# ControlBoardEsp.net
KiCad netlist of a schematic drawn in EAGLE
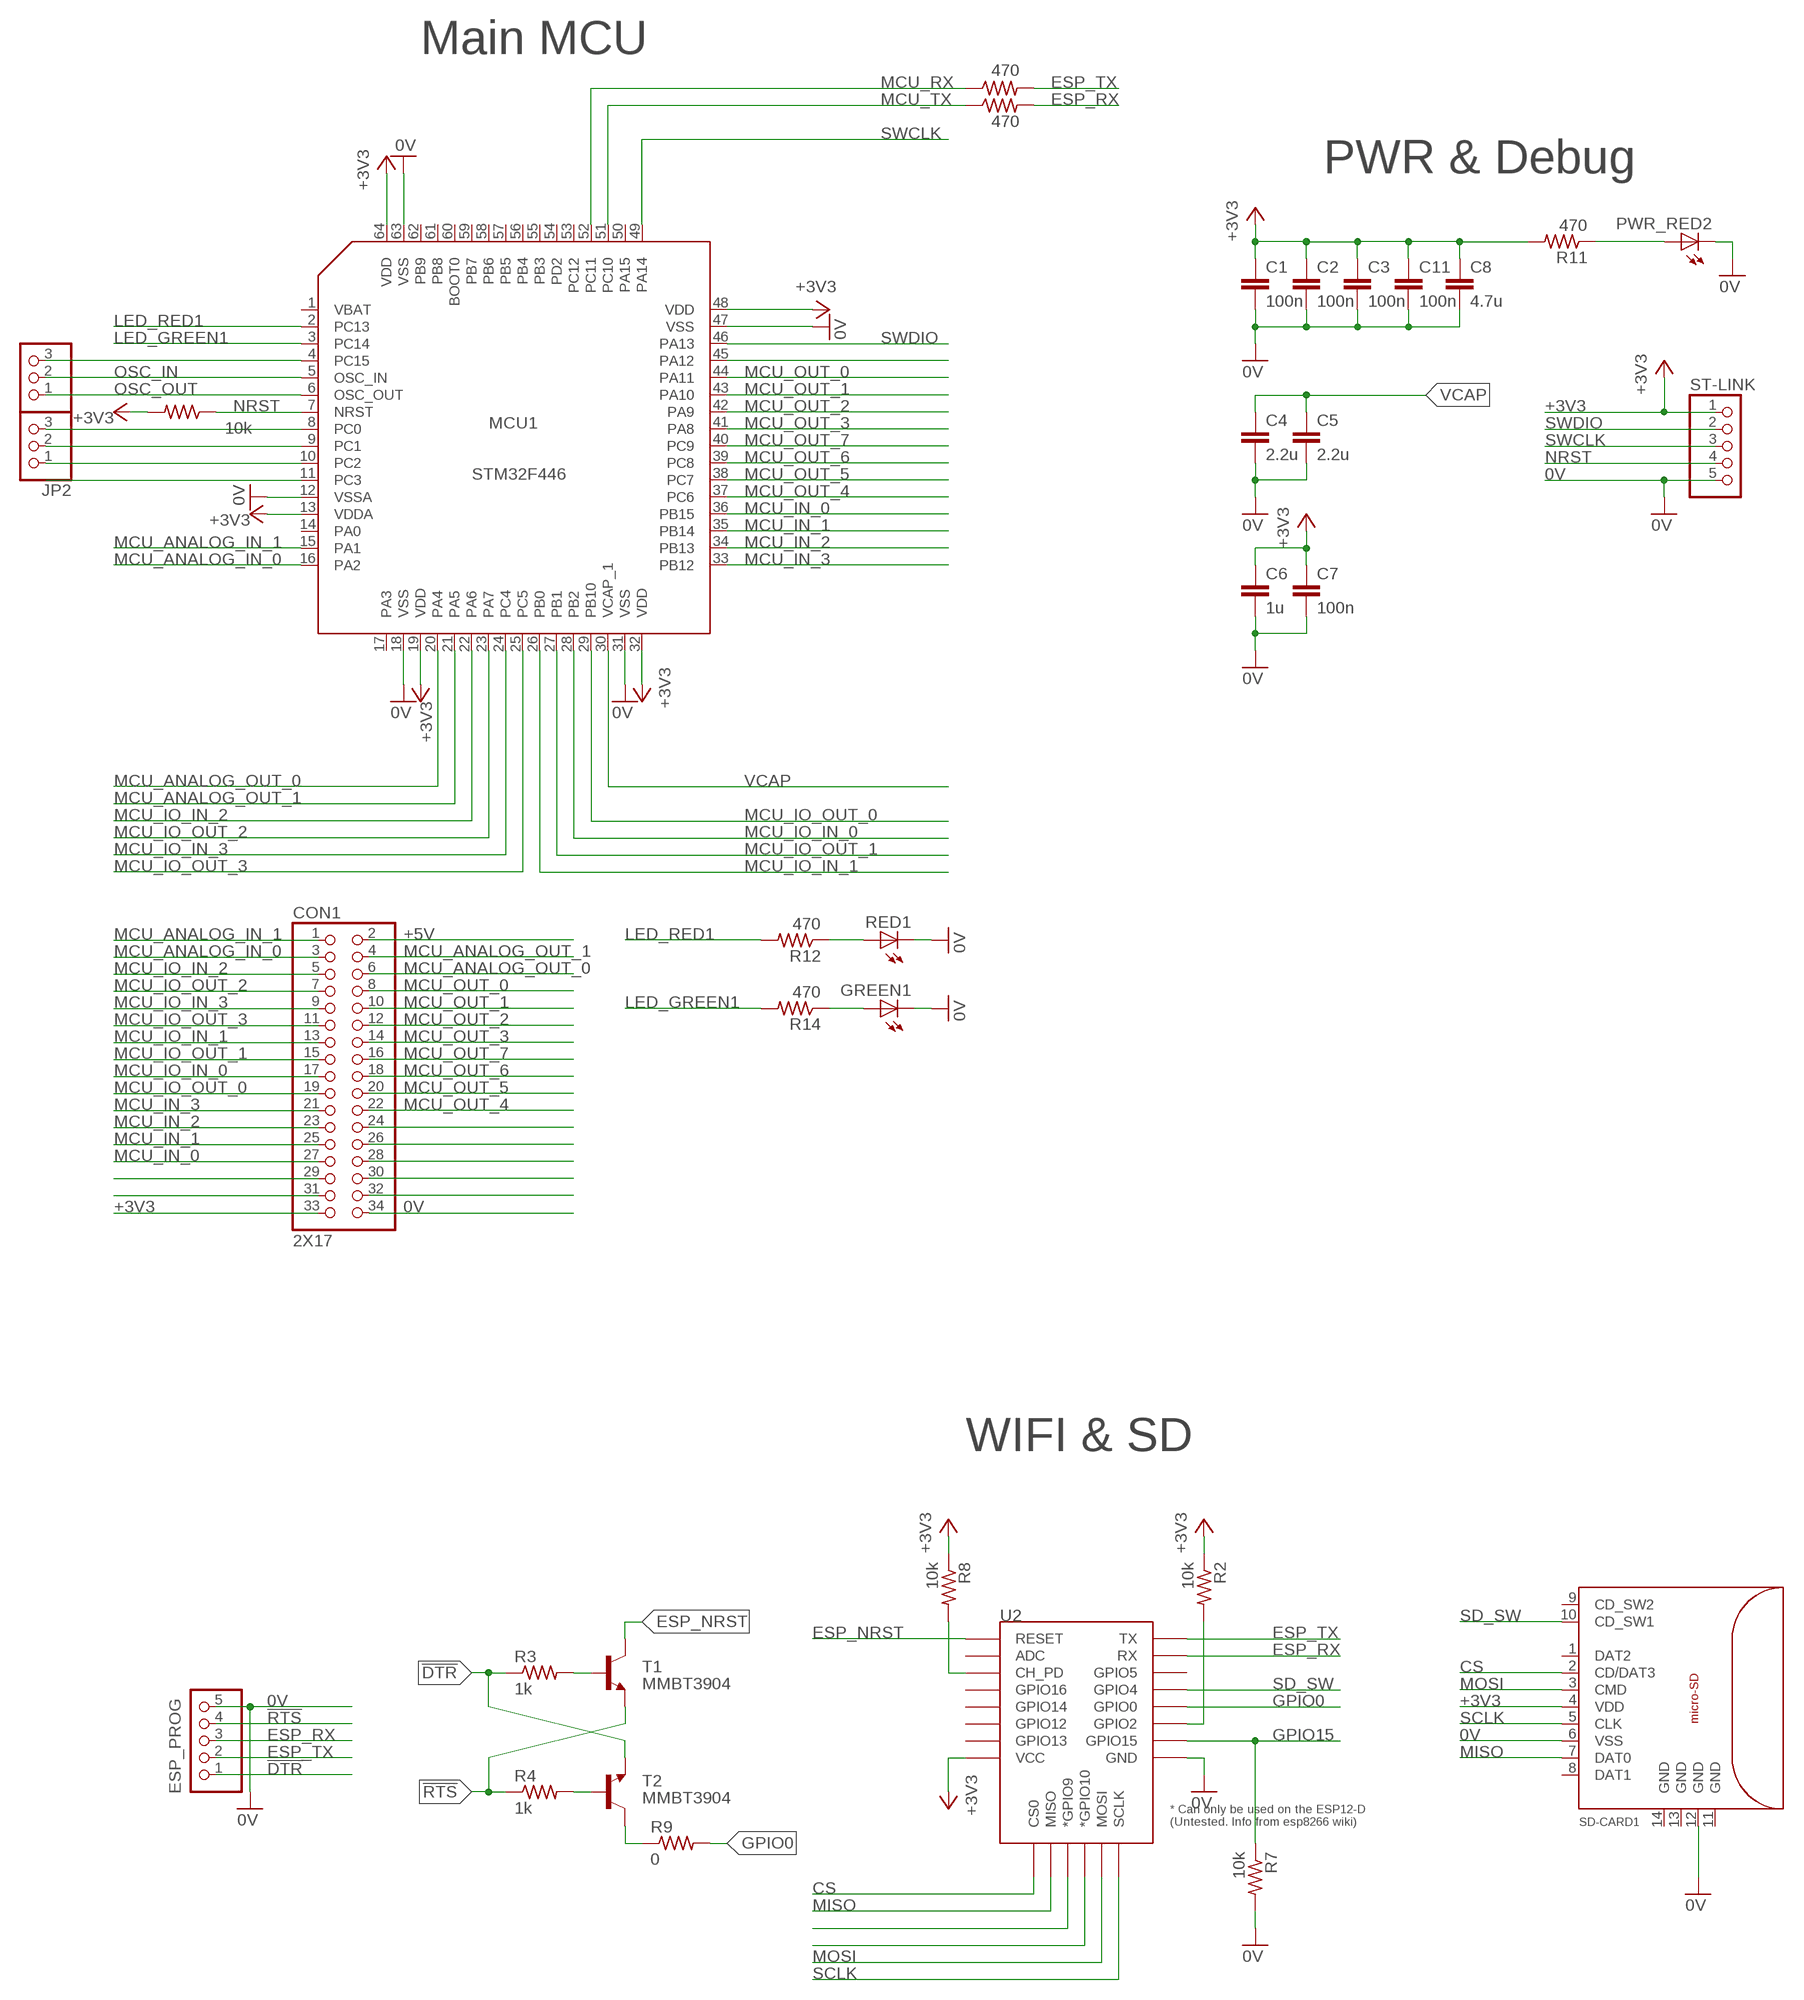
[diagram p0: schematic, sheet 1]

(export (version "E")
  (design (tool "Eeschema 10.0.6"))
  (components
    (comp (ref "C1")
      (value "100n")
      (footprint "eagle-import:C0402")
      (libsource (lib "eagle-import") (part "C-EUC0402"))
    )
    (comp (ref "C2")
      (value "100n")
      (footprint "eagle-import:C0402")
      (libsource (lib "eagle-import") (part "C-EUC0402"))
    )
    (comp (ref "C3")
      (value "100n")
      (footprint "eagle-import:C0402")
      (libsource (lib "eagle-import") (part "C-EUC0402"))
    )
    (comp (ref "C4")
      (value "2.2u")
      (footprint "eagle-import:C0402")
      (libsource (lib "eagle-import") (part "C-EUC0402"))
    )
    (comp (ref "C5")
      (value "2.2u")
      (footprint "eagle-import:C0402")
      (libsource (lib "eagle-import") (part "C-EUC0402"))
    )
    (comp (ref "C6")
      (value "1u")
      (footprint "eagle-import:C0402")
      (libsource (lib "eagle-import") (part "C-EUC0402"))
    )
    (comp (ref "C7")
      (value "100n")
      (footprint "eagle-import:C0402")
      (libsource (lib "eagle-import") (part "C-EUC0402"))
    )
    (comp (ref "C8")
      (value "4.7u")
      (footprint "eagle-import:C0402")
      (libsource (lib "eagle-import") (part "C-EUC0402"))
    )
    (comp (ref "C11")
      (value "100n")
      (footprint "eagle-import:C0402")
      (libsource (lib "eagle-import") (part "C-EUC0402"))
    )
    (comp (ref "CON1")
      (value "2X17")
      (footprint "eagle-import:2X17")
      (libsource (lib "eagle-import") (part "2X17"))
    )
    (comp (ref "ESP_PROG")
      (value "PINHD-1X5")
      (footprint "eagle-import:1X05")
      (libsource (lib "eagle-import") (part "PINHD-1X5"))
    )
    (comp (ref "GREEN1")
      (value "LEDCHIP-LED0805")
      (footprint "eagle-import:CHIP-LED0805")
      (libsource (lib "eagle-import") (part "LEDCHIP-LED0805"))
    )
    (comp (ref "JP1")
      (value "PINHD-1X3")
      (footprint "eagle-import:1X03")
      (libsource (lib "eagle-import") (part "PINHD-1X3"))
    )
    (comp (ref "JP2")
      (value "PINHD-1X3")
      (footprint "eagle-import:1X03")
      (libsource (lib "eagle-import") (part "PINHD-1X3"))
    )
    (comp (ref "MCU1")
      (value "STM32F446")
      (footprint "eagle-import:LQFP-64")
      (libsource (lib "eagle-import") (part "STM32F446"))
    )
    (comp (ref "PWR_RED2")
      (value "LEDCHIP-LED0805")
      (footprint "eagle-import:CHIP-LED0805")
      (libsource (lib "eagle-import") (part "LEDCHIP-LED0805"))
    )
    (comp (ref "R1")
      (value "10k")
      (footprint "eagle-import:R0402")
      (libsource (lib "eagle-import") (part "R-US_R0402"))
    )
    (comp (ref "R2")
      (value "10k")
      (footprint "eagle-import:R0402")
      (libsource (lib "eagle-import") (part "R-US_R0402"))
    )
    (comp (ref "R3")
      (value "1k")
      (footprint "eagle-import:R0402")
      (libsource (lib "eagle-import") (part "R-US_R0402"))
    )
    (comp (ref "R4")
      (value "1k")
      (footprint "eagle-import:R1206")
      (libsource (lib "eagle-import") (part "R-US_R1206"))
    )
    (comp (ref "R5")
      (value "470")
      (footprint "eagle-import:R0402")
      (libsource (lib "eagle-import") (part "R-US_R0402"))
    )
    (comp (ref "R6")
      (value "470")
      (footprint "eagle-import:R0402")
      (libsource (lib "eagle-import") (part "R-US_R0402"))
    )
    (comp (ref "R7")
      (value "10k")
      (footprint "eagle-import:R0402")
      (libsource (lib "eagle-import") (part "R-US_R0402"))
    )
    (comp (ref "R8")
      (value "10k")
      (footprint "eagle-import:R0402")
      (libsource (lib "eagle-import") (part "R-US_R0402"))
    )
    (comp (ref "R9")
      (value "0")
      (footprint "eagle-import:R1206")
      (libsource (lib "eagle-import") (part "R-US_R1206"))
    )
    (comp (ref "R11")
      (value "470")
      (footprint "eagle-import:R0402")
      (libsource (lib "eagle-import") (part "R-US_R0402"))
    )
    (comp (ref "R12")
      (value "470")
      (footprint "eagle-import:R0402")
      (libsource (lib "eagle-import") (part "R-US_R0402"))
    )
    (comp (ref "R14")
      (value "470")
      (footprint "eagle-import:R0402")
      (libsource (lib "eagle-import") (part "R-US_R0402"))
    )
    (comp (ref "RED1")
      (value "LEDCHIP-LED0805")
      (footprint "eagle-import:CHIP-LED0805")
      (libsource (lib "eagle-import") (part "LEDCHIP-LED0805"))
    )
    (comp (ref "SD-CARD1")
      (value "MICRO-SD")
      (footprint "eagle-import:MICRO_SD_FOOTPRINT")
      (libsource (lib "eagle-import") (part "MICRO-SD"))
    )
    (comp (ref "ST-LINK")
      (value "PINHD-1X5")
      (footprint "eagle-import:1X05")
      (libsource (lib "eagle-import") (part "PINHD-1X5"))
    )
    (comp (ref "T1")
      (value "MMBT3904")
      (footprint "eagle-import:SOT23-BEC")
      (libsource (lib "eagle-import") (part "-NPN-SOT23-BECMMBT3904LT1"))
    )
    (comp (ref "T2")
      (value "MMBT3904")
      (footprint "eagle-import:SOT23-BEC")
      (libsource (lib "eagle-import") (part "-NPN-SOT23-BECMMBT3904LT1"))
    )
    (comp (ref "U2")
      (value "ESP12ESMD")
      (footprint "eagle-import:ESP12E-SMD")
      (libsource (lib "eagle-import") (part "ESP12ESMD"))
    )
  )
  (nets
    (net (code "1") (name "+3V3") (class "Default")
      (node (ref "C1") (pin "1") (pinfunction "1_1") (pintype "passive"))
      (node (ref "C11") (pin "1") (pinfunction "1_1") (pintype "passive"))
      (node (ref "C2") (pin "1") (pinfunction "1_1") (pintype "passive"))
      (node (ref "C3") (pin "1") (pinfunction "1_1") (pintype "passive"))
      (node (ref "C6") (pin "1") (pinfunction "1_1") (pintype "passive"))
      (node (ref "C7") (pin "1") (pinfunction "1_1") (pintype "passive"))
      (node (ref "C8") (pin "1") (pinfunction "1_1") (pintype "passive"))
      (node (ref "CON1") (pin "33") (pinfunction "33_33") (pintype "passive"))
      (node (ref "MCU1") (pin "13") (pinfunction "VDDA_13") (pintype "bidirectional"))
      (node (ref "MCU1") (pin "19") (pinfunction "VDD_19") (pintype "bidirectional"))
      (node (ref "MCU1") (pin "32") (pinfunction "VDD_32") (pintype "bidirectional"))
      (node (ref "MCU1") (pin "48") (pinfunction "VDD_48") (pintype "bidirectional"))
      (node (ref "MCU1") (pin "64") (pinfunction "VDD_64") (pintype "bidirectional"))
      (node (ref "R1") (pin "2") (pinfunction "2_2") (pintype "passive"))
      (node (ref "R11") (pin "2") (pinfunction "2_2") (pintype "passive"))
      (node (ref "R2") (pin "1") (pinfunction "1_1") (pintype "passive"))
      (node (ref "R8") (pin "1") (pinfunction "1_1") (pintype "passive"))
      (node (ref "SD-CARD1") (pin "4") (pinfunction "VDD_4") (pintype "bidirectional"))
      (node (ref "ST-LINK") (pin "1") (pinfunction "1_1") (pintype "passive"))
      (node (ref "U2") (pin "VCC") (pinfunction "VCC_VCC") (pintype "bidirectional"))
    )
    (net (code "2") (name "/+5V") (class "Default")
      (node (ref "CON1") (pin "2") (pinfunction "2_2") (pintype "passive"))
    )
    (net (code "3") (name "/CS") (class "Default")
      (node (ref "SD-CARD1") (pin "2") (pinfunction "CD/DAT3_2") (pintype "bidirectional"))
      (node (ref "U2") (pin "CS0") (pinfunction "CS0_CS0") (pintype "bidirectional"))
    )
    (net (code "4") (name "/ESP_RX") (class "Default")
      (node (ref "ESP_PROG") (pin "3") (pinfunction "3_3") (pintype "passive"))
      (node (ref "R6") (pin "2") (pinfunction "2_2") (pintype "passive"))
      (node (ref "U2") (pin "RXD0") (pinfunction "RX_RXD0") (pintype "bidirectional"))
    )
    (net (code "5") (name "/ESP_TX") (class "Default")
      (node (ref "ESP_PROG") (pin "2") (pinfunction "2_2") (pintype "passive"))
      (node (ref "R5") (pin "2") (pinfunction "2_2") (pintype "passive"))
      (node (ref "U2") (pin "TXD0") (pinfunction "TX_TXD0") (pintype "bidirectional"))
    )
    (net (code "6") (name "/GPIO15") (class "Default")
      (node (ref "R7") (pin "1") (pinfunction "1_1") (pintype "passive"))
      (node (ref "U2") (pin "GPIO15") (pinfunction "GPIO15_GPIO15") (pintype "bidirectional"))
    )
    (net (code "7") (name "/LED_GREEN1") (class "Default")
      (node (ref "MCU1") (pin "3") (pinfunction "PC14_3") (pintype "bidirectional"))
      (node (ref "R14") (pin "2") (pinfunction "2_2") (pintype "passive"))
    )
    (net (code "8") (name "/LED_RED1") (class "Default")
      (node (ref "MCU1") (pin "2") (pinfunction "PC13_2") (pintype "bidirectional"))
      (node (ref "R12") (pin "2") (pinfunction "2_2") (pintype "passive"))
    )
    (net (code "9") (name "/MCU_ANALOG_IN_0") (class "Default")
      (node (ref "CON1") (pin "3") (pinfunction "3_3") (pintype "passive"))
      (node (ref "MCU1") (pin "16") (pinfunction "PA2_16") (pintype "bidirectional"))
    )
    (net (code "10") (name "/MCU_ANALOG_IN_1") (class "Default")
      (node (ref "CON1") (pin "1") (pinfunction "1_1") (pintype "passive"))
      (node (ref "MCU1") (pin "15") (pinfunction "PA1_15") (pintype "bidirectional"))
    )
    (net (code "11") (name "/MCU_ANALOG_OUT_0") (class "Default")
      (node (ref "CON1") (pin "6") (pinfunction "6_6") (pintype "passive"))
      (node (ref "MCU1") (pin "20") (pinfunction "PA4_20") (pintype "bidirectional"))
    )
    (net (code "12") (name "/MCU_ANALOG_OUT_1") (class "Default")
      (node (ref "CON1") (pin "4") (pinfunction "4_4") (pintype "passive"))
      (node (ref "MCU1") (pin "21") (pinfunction "PA5_21") (pintype "bidirectional"))
    )
    (net (code "13") (name "/MCU_IN_0") (class "Default")
      (node (ref "CON1") (pin "27") (pinfunction "27_27") (pintype "passive"))
      (node (ref "MCU1") (pin "36") (pinfunction "PB15_36") (pintype "bidirectional"))
    )
    (net (code "14") (name "/MCU_IN_1") (class "Default")
      (node (ref "CON1") (pin "25") (pinfunction "25_25") (pintype "passive"))
      (node (ref "MCU1") (pin "35") (pinfunction "PB14_35") (pintype "bidirectional"))
    )
    (net (code "15") (name "/MCU_IN_2") (class "Default")
      (node (ref "CON1") (pin "23") (pinfunction "23_23") (pintype "passive"))
      (node (ref "MCU1") (pin "34") (pinfunction "PB13_34") (pintype "bidirectional"))
    )
    (net (code "16") (name "/MCU_IN_3") (class "Default")
      (node (ref "CON1") (pin "21") (pinfunction "21_21") (pintype "passive"))
      (node (ref "MCU1") (pin "33") (pinfunction "PB12_33") (pintype "bidirectional"))
    )
    (net (code "17") (name "/MCU_IO_IN_0") (class "Default")
      (node (ref "CON1") (pin "17") (pinfunction "17_17") (pintype "passive"))
      (node (ref "MCU1") (pin "28") (pinfunction "PB2_28") (pintype "bidirectional"))
    )
    (net (code "18") (name "/MCU_IO_IN_1") (class "Default")
      (node (ref "CON1") (pin "13") (pinfunction "13_13") (pintype "passive"))
      (node (ref "MCU1") (pin "26") (pinfunction "PB0_26") (pintype "bidirectional"))
    )
    (net (code "19") (name "/MCU_IO_IN_2") (class "Default")
      (node (ref "CON1") (pin "5") (pinfunction "5_5") (pintype "passive"))
      (node (ref "MCU1") (pin "22") (pinfunction "PA6_22") (pintype "bidirectional"))
    )
    (net (code "20") (name "/MCU_IO_IN_3") (class "Default")
      (node (ref "CON1") (pin "9") (pinfunction "9_9") (pintype "passive"))
      (node (ref "MCU1") (pin "24") (pinfunction "PC4_24") (pintype "bidirectional"))
    )
    (net (code "21") (name "/MCU_IO_OUT_0") (class "Default")
      (node (ref "CON1") (pin "19") (pinfunction "19_19") (pintype "passive"))
      (node (ref "MCU1") (pin "29") (pinfunction "PB10_29") (pintype "bidirectional"))
    )
    (net (code "22") (name "/MCU_IO_OUT_1") (class "Default")
      (node (ref "CON1") (pin "15") (pinfunction "15_15") (pintype "passive"))
      (node (ref "MCU1") (pin "27") (pinfunction "PB1_27") (pintype "bidirectional"))
    )
    (net (code "23") (name "/MCU_IO_OUT_2") (class "Default")
      (node (ref "CON1") (pin "7") (pinfunction "7_7") (pintype "passive"))
      (node (ref "MCU1") (pin "23") (pinfunction "PA7_23") (pintype "bidirectional"))
    )
    (net (code "24") (name "/MCU_IO_OUT_3") (class "Default")
      (node (ref "CON1") (pin "11") (pinfunction "11_11") (pintype "passive"))
      (node (ref "MCU1") (pin "25") (pinfunction "PC5_25") (pintype "bidirectional"))
    )
    (net (code "25") (name "/MCU_OUT_0") (class "Default")
      (node (ref "CON1") (pin "8") (pinfunction "8_8") (pintype "passive"))
      (node (ref "MCU1") (pin "44") (pinfunction "PA11_44") (pintype "bidirectional"))
    )
    (net (code "26") (name "/MCU_OUT_1") (class "Default")
      (node (ref "CON1") (pin "10") (pinfunction "10_10") (pintype "passive"))
      (node (ref "MCU1") (pin "43") (pinfunction "PA10_43") (pintype "bidirectional"))
    )
    (net (code "27") (name "/MCU_OUT_2") (class "Default")
      (node (ref "CON1") (pin "12") (pinfunction "12_12") (pintype "passive"))
      (node (ref "MCU1") (pin "42") (pinfunction "PA9_42") (pintype "bidirectional"))
    )
    (net (code "28") (name "/MCU_OUT_3") (class "Default")
      (node (ref "CON1") (pin "14") (pinfunction "14_14") (pintype "passive"))
      (node (ref "MCU1") (pin "41") (pinfunction "PA8_41") (pintype "bidirectional"))
    )
    (net (code "29") (name "/MCU_OUT_4") (class "Default")
      (node (ref "CON1") (pin "22") (pinfunction "22_22") (pintype "passive"))
      (node (ref "MCU1") (pin "37") (pinfunction "PC6_37") (pintype "bidirectional"))
    )
    (net (code "30") (name "/MCU_OUT_5") (class "Default")
      (node (ref "CON1") (pin "20") (pinfunction "20_20") (pintype "passive"))
      (node (ref "MCU1") (pin "38") (pinfunction "PC7_38") (pintype "bidirectional"))
    )
    (net (code "31") (name "/MCU_OUT_6") (class "Default")
      (node (ref "CON1") (pin "18") (pinfunction "18_18") (pintype "passive"))
      (node (ref "MCU1") (pin "39") (pinfunction "PC8_39") (pintype "bidirectional"))
    )
    (net (code "32") (name "/MCU_OUT_7") (class "Default")
      (node (ref "CON1") (pin "16") (pinfunction "16_16") (pintype "passive"))
      (node (ref "MCU1") (pin "40") (pinfunction "PC9_40") (pintype "bidirectional"))
    )
    (net (code "33") (name "/MCU_RX") (class "Default")
      (node (ref "MCU1") (pin "52") (pinfunction "PC11_52") (pintype "bidirectional"))
      (node (ref "R5") (pin "1") (pinfunction "1_1") (pintype "passive"))
    )
    (net (code "34") (name "/MCU_TX") (class "Default")
      (node (ref "MCU1") (pin "51") (pinfunction "PC10_51") (pintype "bidirectional"))
      (node (ref "R6") (pin "1") (pinfunction "1_1") (pintype "passive"))
    )
    (net (code "35") (name "/MISO") (class "Default")
      (node (ref "SD-CARD1") (pin "7") (pinfunction "DAT0_7") (pintype "bidirectional"))
      (node (ref "U2") (pin "MISO") (pinfunction "MISO_MISO") (pintype "bidirectional"))
    )
    (net (code "36") (name "/MOSI") (class "Default")
      (node (ref "SD-CARD1") (pin "3") (pinfunction "CMD_3") (pintype "bidirectional"))
      (node (ref "U2") (pin "MOSI") (pinfunction "MOSI_MOSI") (pintype "bidirectional"))
    )
    (net (code "37") (name "/NRST") (class "Default")
      (node (ref "MCU1") (pin "7") (pinfunction "NRST_7") (pintype "bidirectional"))
      (node (ref "R1") (pin "1") (pinfunction "1_1") (pintype "passive"))
      (node (ref "ST-LINK") (pin "4") (pinfunction "4_4") (pintype "passive"))
    )
    (net (code "38") (name "/OSC_IN") (class "Default")
      (node (ref "JP1") (pin "2") (pinfunction "2_2") (pintype "passive"))
      (node (ref "MCU1") (pin "5") (pinfunction "OSC_IN_5") (pintype "bidirectional"))
    )
    (net (code "39") (name "/OSC_OUT") (class "Default")
      (node (ref "JP1") (pin "1") (pinfunction "1_1") (pintype "passive"))
      (node (ref "MCU1") (pin "6") (pinfunction "OSC_OUT_6") (pintype "bidirectional"))
    )
    (net (code "40") (name "/SCLK") (class "Default")
      (node (ref "SD-CARD1") (pin "5") (pinfunction "CLK_5") (pintype "bidirectional"))
      (node (ref "U2") (pin "SCLK") (pinfunction "SCLK_SCLK") (pintype "bidirectional"))
    )
    (net (code "41") (name "/SD_SW") (class "Default")
      (node (ref "SD-CARD1") (pin "10") (pinfunction "CD_SW1_10") (pintype "bidirectional"))
      (node (ref "U2") (pin "GPIO4") (pinfunction "GPIO4_GPIO4") (pintype "bidirectional"))
    )
    (net (code "42") (name "/SWCLK") (class "Default")
      (node (ref "MCU1") (pin "49") (pinfunction "PA14_49") (pintype "bidirectional"))
      (node (ref "ST-LINK") (pin "3") (pinfunction "3_3") (pintype "passive"))
    )
    (net (code "43") (name "/SWDIO") (class "Default")
      (node (ref "MCU1") (pin "46") (pinfunction "PA13_46") (pintype "bidirectional"))
      (node (ref "ST-LINK") (pin "2") (pinfunction "2_2") (pintype "passive"))
    )
    (net (code "44") (name "/~{DTR}") (class "Default")
      (node (ref "ESP_PROG") (pin "1") (pinfunction "1_1") (pintype "passive"))
      (node (ref "R3") (pin "1") (pinfunction "1_1") (pintype "passive"))
      (node (ref "T2") (pin "E") (pinfunction "E_E") (pintype "passive"))
    )
    (net (code "45") (name "/~{RTS}") (class "Default")
      (node (ref "ESP_PROG") (pin "4") (pinfunction "4_4") (pintype "passive"))
      (node (ref "R4") (pin "1") (pinfunction "1_1") (pintype "passive"))
      (node (ref "T1") (pin "E") (pinfunction "E_E") (pintype "passive"))
    )
    (net (code "46") (name "0V") (class "Default")
      (node (ref "C1") (pin "2") (pinfunction "2_2") (pintype "passive"))
      (node (ref "C11") (pin "2") (pinfunction "2_2") (pintype "passive"))
      (node (ref "C2") (pin "2") (pinfunction "2_2") (pintype "passive"))
      (node (ref "C3") (pin "2") (pinfunction "2_2") (pintype "passive"))
      (node (ref "C4") (pin "2") (pinfunction "2_2") (pintype "passive"))
      (node (ref "C5") (pin "2") (pinfunction "2_2") (pintype "passive"))
      (node (ref "C6") (pin "2") (pinfunction "2_2") (pintype "passive"))
      (node (ref "C7") (pin "2") (pinfunction "2_2") (pintype "passive"))
      (node (ref "C8") (pin "2") (pinfunction "2_2") (pintype "passive"))
      (node (ref "CON1") (pin "34") (pinfunction "34_34") (pintype "passive"))
      (node (ref "ESP_PROG") (pin "5") (pinfunction "5_5") (pintype "passive"))
      (node (ref "GREEN1") (pin "C") (pinfunction "C_C") (pintype "passive"))
      (node (ref "MCU1") (pin "12") (pinfunction "VSSA_12") (pintype "bidirectional"))
      (node (ref "MCU1") (pin "18") (pinfunction "VSS_18") (pintype "bidirectional"))
      (node (ref "MCU1") (pin "31") (pinfunction "VSS_31") (pintype "bidirectional"))
      (node (ref "MCU1") (pin "47") (pinfunction "VSS_47") (pintype "bidirectional"))
      (node (ref "MCU1") (pin "63") (pinfunction "VSS_63") (pintype "bidirectional"))
      (node (ref "PWR_RED2") (pin "C") (pinfunction "C_C") (pintype "passive"))
      (node (ref "R7") (pin "2") (pinfunction "2_2") (pintype "passive"))
      (node (ref "RED1") (pin "C") (pinfunction "C_C") (pintype "passive"))
      (node (ref "SD-CARD1") (pin "12") (pinfunction "GND_12") (pintype "bidirectional"))
      (node (ref "SD-CARD1") (pin "6") (pinfunction "VSS_6") (pintype "bidirectional"))
      (node (ref "ST-LINK") (pin "5") (pinfunction "5_5") (pintype "passive"))
      (node (ref "U2") (pin "GND") (pinfunction "GND_GND") (pintype "bidirectional"))
    )
    (net (code "47") (name "ESP_NRST") (class "Default")
      (node (ref "T1") (pin "C") (pinfunction "C_C") (pintype "passive"))
      (node (ref "U2") (pin "RESET") (pinfunction "RESET_RESET") (pintype "bidirectional"))
    )
    (net (code "48") (name "GPIO0") (class "Default")
      (node (ref "R9") (pin "2") (pinfunction "2_2") (pintype "passive"))
      (node (ref "U2") (pin "GPIO0") (pinfunction "GPIO0_GPIO0") (pintype "bidirectional"))
    )
    (net (code "49") (name "Net-(GREEN1-PadA)") (class "Default")
      (node (ref "GREEN1") (pin "A") (pinfunction "A_A") (pintype "passive"))
      (node (ref "R14") (pin "1") (pinfunction "1_1") (pintype "passive"))
    )
    (net (code "50") (name "Net-(MCU1-PC0)") (class "Default")
      (node (ref "JP2") (pin "3") (pinfunction "3_3") (pintype "passive"))
      (node (ref "MCU1") (pin "8") (pinfunction "PC0_8") (pintype "bidirectional"))
    )
    (net (code "51") (name "Net-(MCU1-PC1)") (class "Default")
      (node (ref "JP2") (pin "2") (pinfunction "2_2") (pintype "passive"))
      (node (ref "MCU1") (pin "9") (pinfunction "PC1_9") (pintype "bidirectional"))
    )
    (net (code "52") (name "Net-(MCU1-PC2)") (class "Default")
      (node (ref "JP2") (pin "1") (pinfunction "1_1") (pintype "passive"))
      (node (ref "MCU1") (pin "10") (pinfunction "PC2_10") (pintype "bidirectional"))
    )
    (net (code "53") (name "Net-(MCU1-PC15)") (class "Default")
      (node (ref "JP1") (pin "3") (pinfunction "3_3") (pintype "passive"))
      (node (ref "MCU1") (pin "4") (pinfunction "PC15_4") (pintype "bidirectional"))
    )
    (net (code "54") (name "Net-(PWR_RED2-PadA)") (class "Default")
      (node (ref "PWR_RED2") (pin "A") (pinfunction "A_A") (pintype "passive"))
      (node (ref "R11") (pin "1") (pinfunction "1_1") (pintype "passive"))
    )
    (net (code "55") (name "Net-(R2-Pad2)") (class "Default")
      (node (ref "R2") (pin "2") (pinfunction "2_2") (pintype "passive"))
      (node (ref "U2") (pin "GPIO2") (pinfunction "GPIO2_GPIO2") (pintype "bidirectional"))
    )
    (net (code "56") (name "Net-(R3-Pad2)") (class "Default")
      (node (ref "R3") (pin "2") (pinfunction "2_2") (pintype "passive"))
      (node (ref "T1") (pin "B") (pinfunction "B_B") (pintype "passive"))
    )
    (net (code "57") (name "Net-(R4-Pad2)") (class "Default")
      (node (ref "R4") (pin "2") (pinfunction "2_2") (pintype "passive"))
      (node (ref "T2") (pin "B") (pinfunction "B_B") (pintype "passive"))
    )
    (net (code "58") (name "Net-(R8-Pad2)") (class "Default")
      (node (ref "R8") (pin "2") (pinfunction "2_2") (pintype "passive"))
      (node (ref "U2") (pin "CH_PD") (pinfunction "CH_PD_CH_PD") (pintype "bidirectional"))
    )
    (net (code "59") (name "Net-(R9-Pad1)") (class "Default")
      (node (ref "R9") (pin "1") (pinfunction "1_1") (pintype "passive"))
      (node (ref "T2") (pin "C") (pinfunction "C_C") (pintype "passive"))
    )
    (net (code "60") (name "Net-(R12-Pad1)") (class "Default")
      (node (ref "R12") (pin "1") (pinfunction "1_1") (pintype "passive"))
      (node (ref "RED1") (pin "A") (pinfunction "A_A") (pintype "passive"))
    )
    (net (code "61") (name "VCAP") (class "Default")
      (node (ref "C4") (pin "1") (pinfunction "1_1") (pintype "passive"))
      (node (ref "C5") (pin "1") (pinfunction "1_1") (pintype "passive"))
      (node (ref "MCU1") (pin "30") (pinfunction "VCAP_1_30") (pintype "bidirectional"))
    )
    (net (code "62") (name "unconnected-(CON1-Pad24)") (class "Default")
      (node (ref "CON1") (pin "24") (pinfunction "24_24") (pintype "passive"))
    )
    (net (code "63") (name "unconnected-(CON1-Pad26)") (class "Default")
      (node (ref "CON1") (pin "26") (pinfunction "26_26") (pintype "passive"))
    )
    (net (code "64") (name "unconnected-(CON1-Pad28)") (class "Default")
      (node (ref "CON1") (pin "28") (pinfunction "28_28") (pintype "passive"))
    )
    (net (code "65") (name "unconnected-(CON1-Pad29)") (class "Default")
      (node (ref "CON1") (pin "29") (pinfunction "29_29") (pintype "passive"))
    )
    (net (code "66") (name "unconnected-(CON1-Pad30)") (class "Default")
      (node (ref "CON1") (pin "30") (pinfunction "30_30") (pintype "passive"))
    )
    (net (code "67") (name "unconnected-(CON1-Pad31)") (class "Default")
      (node (ref "CON1") (pin "31") (pinfunction "31_31") (pintype "passive"))
    )
    (net (code "68") (name "unconnected-(CON1-Pad32)") (class "Default")
      (node (ref "CON1") (pin "32") (pinfunction "32_32") (pintype "passive"))
    )
    (net (code "69") (name "unconnected-(MCU1-BOOT0-Pad60)") (class "Default")
      (node (ref "MCU1") (pin "60") (pinfunction "BOOT0_60") (pintype "bidirectional"))
    )
    (net (code "70") (name "unconnected-(MCU1-PA0-Pad14)") (class "Default")
      (node (ref "MCU1") (pin "14") (pinfunction "PA0_14") (pintype "bidirectional"))
    )
    (net (code "71") (name "unconnected-(MCU1-PA3-Pad17)") (class "Default")
      (node (ref "MCU1") (pin "17") (pinfunction "PA3_17") (pintype "bidirectional"))
    )
    (net (code "72") (name "unconnected-(MCU1-PA12-Pad45)") (class "Default")
      (node (ref "MCU1") (pin "45") (pinfunction "PA12_45") (pintype "bidirectional"))
    )
    (net (code "73") (name "unconnected-(MCU1-PA15-Pad50)") (class "Default")
      (node (ref "MCU1") (pin "50") (pinfunction "PA15_50") (pintype "bidirectional"))
    )
    (net (code "74") (name "unconnected-(MCU1-PB3-Pad55)") (class "Default")
      (node (ref "MCU1") (pin "55") (pinfunction "PB3_55") (pintype "bidirectional"))
    )
    (net (code "75") (name "unconnected-(MCU1-PB4-Pad56)") (class "Default")
      (node (ref "MCU1") (pin "56") (pinfunction "PB4_56") (pintype "bidirectional"))
    )
    (net (code "76") (name "unconnected-(MCU1-PB5-Pad57)") (class "Default")
      (node (ref "MCU1") (pin "57") (pinfunction "PB5_57") (pintype "bidirectional"))
    )
    (net (code "77") (name "unconnected-(MCU1-PB6-Pad58)") (class "Default")
      (node (ref "MCU1") (pin "58") (pinfunction "PB6_58") (pintype "bidirectional"))
    )
    (net (code "78") (name "unconnected-(MCU1-PB7-Pad59)") (class "Default")
      (node (ref "MCU1") (pin "59") (pinfunction "PB7_59") (pintype "bidirectional"))
    )
    (net (code "79") (name "unconnected-(MCU1-PB8-Pad61)") (class "Default")
      (node (ref "MCU1") (pin "61") (pinfunction "PB8_61") (pintype "bidirectional"))
    )
    (net (code "80") (name "unconnected-(MCU1-PB9-Pad62)") (class "Default")
      (node (ref "MCU1") (pin "62") (pinfunction "PB9_62") (pintype "bidirectional"))
    )
    (net (code "81") (name "unconnected-(MCU1-PC3-Pad11)") (class "Default")
      (node (ref "MCU1") (pin "11") (pinfunction "PC3_11") (pintype "bidirectional"))
    )
    (net (code "82") (name "unconnected-(MCU1-PC12-Pad53)") (class "Default")
      (node (ref "MCU1") (pin "53") (pinfunction "PC12_53") (pintype "bidirectional"))
    )
    (net (code "83") (name "unconnected-(MCU1-PD2-Pad54)") (class "Default")
      (node (ref "MCU1") (pin "54") (pinfunction "PD2_54") (pintype "bidirectional"))
    )
    (net (code "84") (name "unconnected-(MCU1-VBAT-Pad1)") (class "Default")
      (node (ref "MCU1") (pin "1") (pinfunction "VBAT_1") (pintype "bidirectional"))
    )
    (net (code "85") (name "unconnected-(SD-CARD1-CD_SW2-Pad9)") (class "Default")
      (node (ref "SD-CARD1") (pin "9") (pinfunction "CD_SW2_9") (pintype "bidirectional"))
    )
    (net (code "86") (name "unconnected-(SD-CARD1-DAT1-Pad8)") (class "Default")
      (node (ref "SD-CARD1") (pin "8") (pinfunction "DAT1_8") (pintype "bidirectional"))
    )
    (net (code "87") (name "unconnected-(SD-CARD1-DAT2-Pad1)") (class "Default")
      (node (ref "SD-CARD1") (pin "1") (pinfunction "DAT2_1") (pintype "bidirectional"))
    )
    (net (code "88") (name "unconnected-(SD-CARD1-GND-Pad11)") (class "Default")
      (node (ref "SD-CARD1") (pin "11") (pinfunction "GND_11") (pintype "bidirectional"))
    )
    (net (code "89") (name "unconnected-(SD-CARD1-GND-Pad13)") (class "Default")
      (node (ref "SD-CARD1") (pin "13") (pinfunction "GND_13") (pintype "bidirectional"))
    )
    (net (code "90") (name "unconnected-(SD-CARD1-GND-Pad14)") (class "Default")
      (node (ref "SD-CARD1") (pin "14") (pinfunction "GND_14") (pintype "bidirectional"))
    )
    (net (code "91") (name "unconnected-(U2-*GPIO9-PadGPIO9)") (class "Default")
      (node (ref "U2") (pin "GPIO9") (pinfunction "*GPIO9_GPIO9") (pintype "bidirectional"))
    )
    (net (code "92") (name "unconnected-(U2-*GPIO10-PadGPIO10)") (class "Default")
      (node (ref "U2") (pin "GPIO10") (pinfunction "*GPIO10_GPIO10") (pintype "bidirectional"))
    )
    (net (code "93") (name "unconnected-(U2-PadADC)") (class "Default")
      (node (ref "U2") (pin "ADC") (pinfunction "ADC_ADC") (pintype "bidirectional"))
    )
    (net (code "94") (name "unconnected-(U2-PadGPIO5)") (class "Default")
      (node (ref "U2") (pin "GPIO5") (pinfunction "GPIO5_GPIO5") (pintype "bidirectional"))
    )
    (net (code "95") (name "unconnected-(U2-PadGPIO12)") (class "Default")
      (node (ref "U2") (pin "GPIO12") (pinfunction "GPIO12_GPIO12") (pintype "bidirectional"))
    )
    (net (code "96") (name "unconnected-(U2-PadGPIO13)") (class "Default")
      (node (ref "U2") (pin "GPIO13") (pinfunction "GPIO13_GPIO13") (pintype "bidirectional"))
    )
    (net (code "97") (name "unconnected-(U2-PadGPIO14)") (class "Default")
      (node (ref "U2") (pin "GPIO14") (pinfunction "GPIO14_GPIO14") (pintype "bidirectional"))
    )
    (net (code "98") (name "unconnected-(U2-PadGPIO16)") (class "Default")
      (node (ref "U2") (pin "GPIO16") (pinfunction "GPIO16_GPIO16") (pintype "bidirectional"))
    )
  )
)
